# board_back.net
KiCad netlist of a schematic drawn in Altium Designer
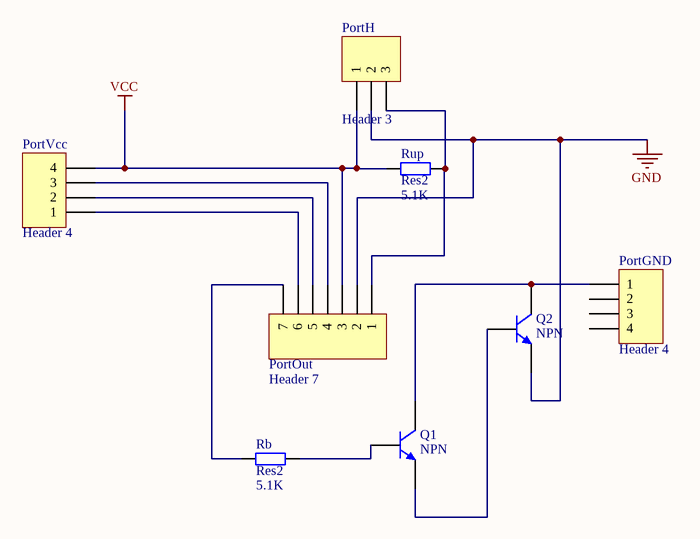
[diagram p0: board_back.SchDoc]

(export (version "E")
  (design (tool "Eeschema 10.0.6"))
  (components
    (comp (ref "PortGND")
      (value "Header 4")
      (footprint "HDR1X4")
      (description "Header, 4-Pin")
      (fields (field (name "PUBLISHER") "Altium Limited"))
      (libsource (lib "Miscellaneous Connectors") (part "Header 4"))
    )
    (comp (ref "PortH")
      (value "Header 3")
      (footprint "HDR1X3")
      (description "Header, 3-Pin")
      (fields (field (name "PUBLISHER") "Altium Limited"))
      (libsource (lib "Miscellaneous Connectors") (part "Header 3"))
    )
    (comp (ref "PortOut")
      (value "Header 7")
      (footprint "HDR1X7")
      (description "Header, 7-Pin")
      (fields (field (name "PUBLISHER") "Altium Limited"))
      (libsource (lib "Miscellaneous Connectors") (part "Header 7"))
    )
    (comp (ref "PortVcc")
      (value "Header 4")
      (footprint "HDR1X4")
      (description "Header, 4-Pin")
      (fields (field (name "PUBLISHER") "Altium Limited"))
      (libsource (lib "") (part "Header 4_1"))
    )
    (comp (ref "Q1")
      (value "NPN")
      (footprint "TO-226-AA")
      (description "NPN Bipolar Transistor")
      (fields (field (name "PUBLISHER") "Altium Limited"))
      (libsource (lib "Miscellaneous Devices") (part "NPN"))
    )
    (comp (ref "Q2")
      (value "NPN")
      (footprint "TO-226-AA")
      (description "NPN Bipolar Transistor")
      (fields (field (name "PUBLISHER") "Altium Limited"))
      (libsource (lib "Miscellaneous Devices") (part "NPN"))
    )
    (comp (ref "Rb")
      (value "Res2")
      (footprint "AXIAL-0.4")
      (description "Resistor")
      (fields (field (name "ALTIUM_VALUE") "5.1K") (field (name "PUBLISHER") "Altium Limited"))
      (libsource (lib "Miscellaneous Devices") (part "Res2"))
    )
    (comp (ref "Rup")
      (value "Res2")
      (footprint "AXIAL-0.4")
      (description "Resistor")
      (fields (field (name "ALTIUM_VALUE") "5.1K") (field (name "PUBLISHER") "Altium Limited"))
      (libsource (lib "Miscellaneous Devices") (part "Res2"))
    )
  )
  (nets
    (net (code "1") (name "GND") (class "Default")
      (node (ref "PortH") (pin "2") (pinfunction "2_2") (pintype "passive"))
      (node (ref "PortOut") (pin "2") (pinfunction "2_2") (pintype "passive"))
      (node (ref "Q2") (pin "3") (pinfunction "E_3") (pintype "passive"))
    )
    (net (code "2") (name "Net-(PortH-Pad3)") (class "Default")
      (node (ref "PortH") (pin "3") (pinfunction "3_3") (pintype "passive"))
      (node (ref "PortOut") (pin "1") (pinfunction "1_1") (pintype "passive"))
      (node (ref "Rup") (pin "2") (pinfunction "2_2") (pintype "passive"))
    )
    (net (code "3") (name "Net-(PortOut-Pad4)") (class "Default")
      (node (ref "PortOut") (pin "4") (pinfunction "4_4") (pintype "passive"))
      (node (ref "PortVcc") (pin "3") (pinfunction "3_3") (pintype "passive"))
    )
    (net (code "4") (name "Net-(PortOut-Pad5)") (class "Default")
      (node (ref "PortOut") (pin "5") (pinfunction "5_5") (pintype "passive"))
      (node (ref "PortVcc") (pin "2") (pinfunction "2_2") (pintype "passive"))
    )
    (net (code "5") (name "Net-(PortOut-Pad6)") (class "Default")
      (node (ref "PortOut") (pin "6") (pinfunction "6_6") (pintype "passive"))
      (node (ref "PortVcc") (pin "1") (pinfunction "1_1") (pintype "passive"))
    )
    (net (code "6") (name "Net-(PortOut-Pad7)") (class "Default")
      (node (ref "PortOut") (pin "7") (pinfunction "7_7") (pintype "passive"))
      (node (ref "Rb") (pin "1") (pinfunction "1_1") (pintype "passive"))
    )
    (net (code "7") (name "Net-(Q1-B)") (class "Default")
      (node (ref "Q1") (pin "2") (pinfunction "B_2") (pintype "passive"))
      (node (ref "Rb") (pin "2") (pinfunction "2_2") (pintype "passive"))
    )
    (net (code "8") (name "Net-(Q1-C)") (class "Default")
      (node (ref "PortGND") (pin "1") (pinfunction "1_1") (pintype "passive"))
      (node (ref "Q1") (pin "1") (pinfunction "C_1") (pintype "passive"))
      (node (ref "Q2") (pin "1") (pinfunction "C_1") (pintype "passive"))
    )
    (net (code "9") (name "Net-(Q1-E)") (class "Default")
      (node (ref "Q1") (pin "3") (pinfunction "E_3") (pintype "passive"))
      (node (ref "Q2") (pin "2") (pinfunction "B_2") (pintype "passive"))
    )
    (net (code "10") (name "VCC") (class "Default")
      (node (ref "PortH") (pin "1") (pinfunction "1_1") (pintype "passive"))
      (node (ref "PortOut") (pin "3") (pinfunction "3_3") (pintype "passive"))
      (node (ref "PortVcc") (pin "4") (pinfunction "4_4") (pintype "passive"))
      (node (ref "Rup") (pin "1") (pinfunction "1_1") (pintype "passive"))
    )
    (net (code "11") (name "unconnected-(PortGND-Pad2)") (class "Default")
      (node (ref "PortGND") (pin "2") (pinfunction "2_2") (pintype "passive"))
    )
    (net (code "12") (name "unconnected-(PortGND-Pad3)") (class "Default")
      (node (ref "PortGND") (pin "3") (pinfunction "3_3") (pintype "passive"))
    )
    (net (code "13") (name "unconnected-(PortGND-Pad4)") (class "Default")
      (node (ref "PortGND") (pin "4") (pinfunction "4_4") (pintype "passive"))
    )
  )
)
